# soc-conn.net
KiCad netlist of a schematic drawn in Altium Designer
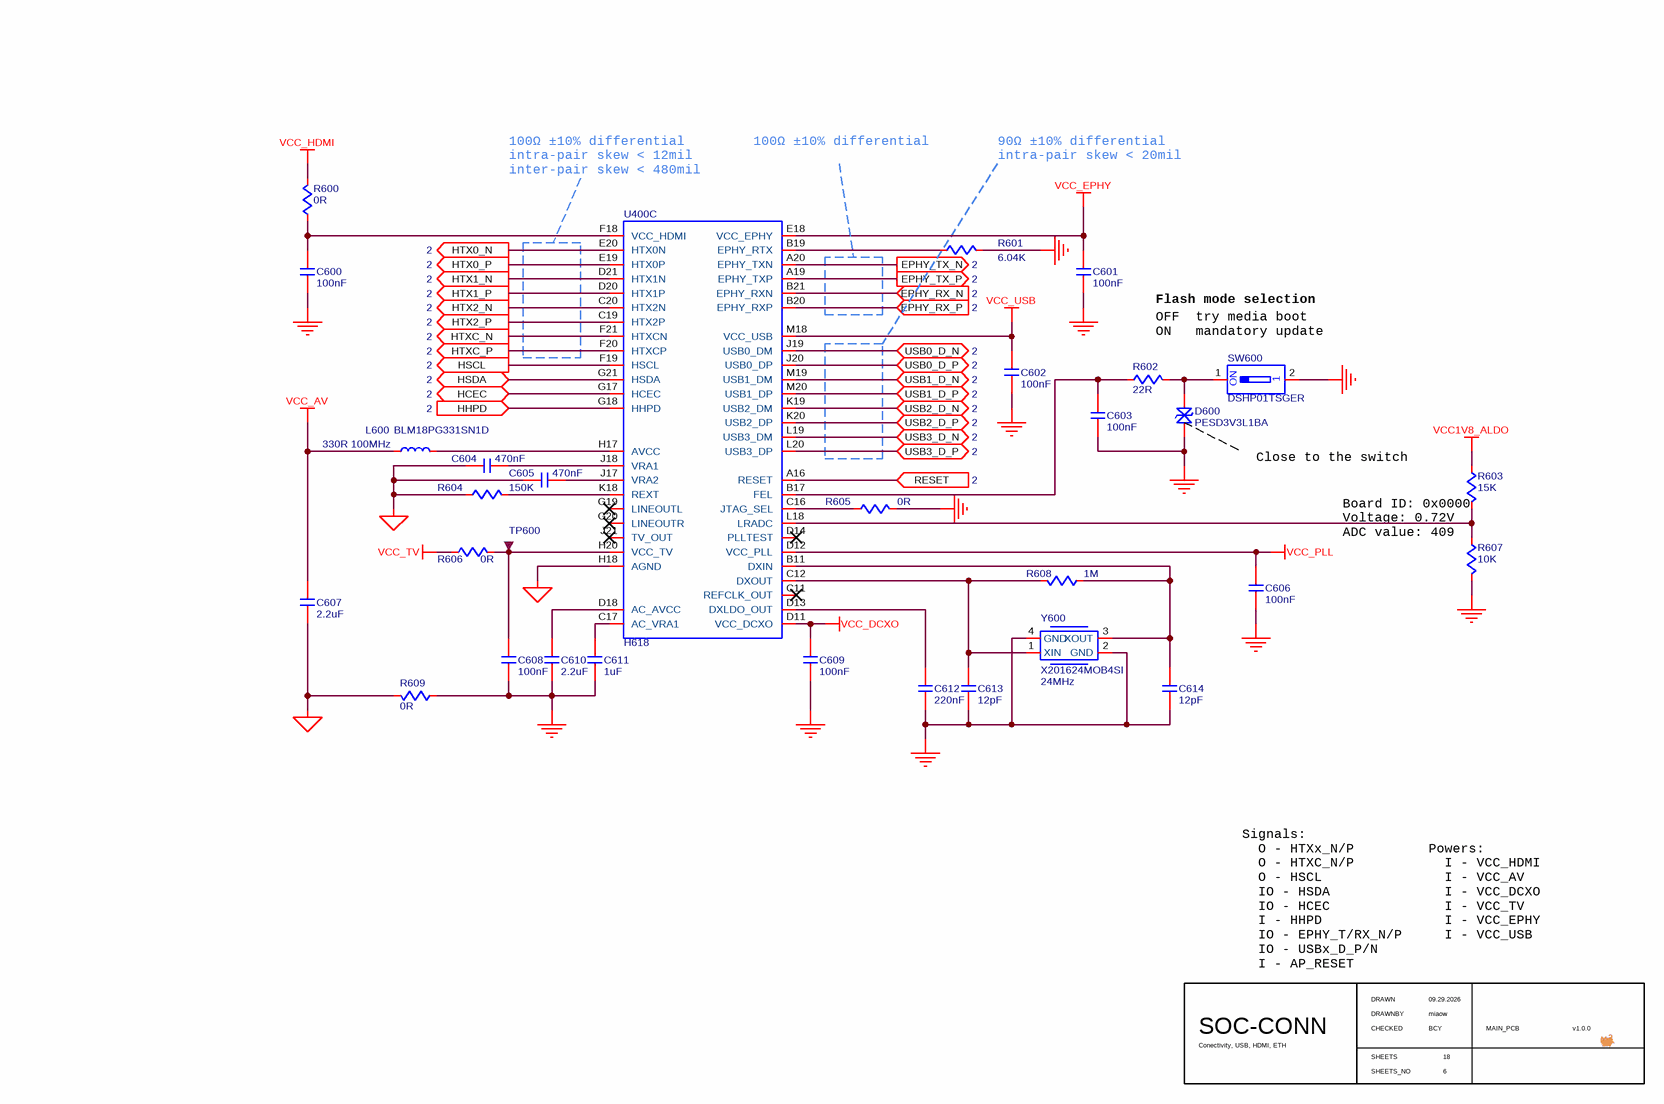
[diagram p0: soc-conn.schdoc]

(export (version "E")
  (design (tool "Eeschema 10.0.6"))
  (components
    (comp (ref "C600")
      (value "100nF")
      (footprint "mw:C0201")
      (fields (field (name "VOLTAGE") "10V") (field (name "Comment") "C-NOMO"))
      (libsource (lib "mw") (part "C-NOMO"))
    )
    (comp (ref "C601")
      (value "100nF")
      (footprint "mw:C0201")
      (fields (field (name "VOLTAGE") "10V") (field (name "Comment") "C-NOMO"))
      (libsource (lib "mw") (part "C-NOMO"))
    )
    (comp (ref "C602")
      (value "100nF")
      (footprint "mw:C0201")
      (fields (field (name "VOLTAGE") "10V") (field (name "Comment") "C-NOMO"))
      (libsource (lib "mw") (part "C-NOMO"))
    )
    (comp (ref "C603")
      (value "100nF")
      (footprint "mw:C0402")
      (fields (field (name "VOLTAGE") "50V") (field (name "Comment") "C-NOMO"))
      (libsource (lib "mw") (part "C-NOMO"))
    )
    (comp (ref "C604")
      (value "470nF")
      (footprint "mw:C0201")
      (fields (field (name "VOLTAGE") "6.3V") (field (name "Comment") "C-NOMO"))
      (libsource (lib "mw") (part "C-NOMO"))
    )
    (comp (ref "C605")
      (value "470nF")
      (footprint "mw:C0201")
      (fields (field (name "VOLTAGE") "6.3V") (field (name "Comment") "C-NOMO"))
      (libsource (lib "mw") (part "C-NOMO"))
    )
    (comp (ref "C606")
      (value "100nF")
      (footprint "mw:C0201")
      (fields (field (name "VOLTAGE") "10V") (field (name "Comment") "C-NOMO"))
      (libsource (lib "mw") (part "C-NOMO"))
    )
    (comp (ref "C607")
      (value "2.2uF")
      (footprint "mw:C0402")
      (fields (field (name "VOLTAGE") "6.3V") (field (name "Comment") "C-NOMO"))
      (libsource (lib "mw") (part "C-NOMO"))
    )
    (comp (ref "C608")
      (value "100nF")
      (footprint "mw:C0201")
      (fields (field (name "VOLTAGE") "10V") (field (name "Comment") "C-NOMO"))
      (libsource (lib "mw") (part "C-NOMO"))
    )
    (comp (ref "C609")
      (value "100nF")
      (footprint "mw:C0201")
      (fields (field (name "VOLTAGE") "10V") (field (name "Comment") "C-NOMO"))
      (libsource (lib "mw") (part "C-NOMO"))
    )
    (comp (ref "C610")
      (value "2.2uF")
      (footprint "mw:C0402")
      (fields (field (name "VOLTAGE") "6.3V") (field (name "Comment") "C-NOMO"))
      (libsource (lib "mw") (part "C-NOMO"))
    )
    (comp (ref "C611")
      (value "1uF")
      (footprint "mw:C0201")
      (fields (field (name "VOLTAGE") "6.3V") (field (name "Comment") "C-NOMO"))
      (libsource (lib "mw") (part "C-NOMO"))
    )
    (comp (ref "C612")
      (value "220nF")
      (footprint "mw:C0201")
      (fields (field (name "VOLTAGE") "6.3V") (field (name "Comment") "C-NOMO"))
      (libsource (lib "mw") (part "C-NOMO"))
    )
    (comp (ref "C613")
      (value "12pF")
      (footprint "mw:C0402")
      (fields (field (name "VOLTAGE") "50V") (field (name "Comment") "C-NOMO"))
      (libsource (lib "mw") (part "C-NOMO"))
    )
    (comp (ref "C614")
      (value "12pF")
      (footprint "mw:C0402")
      (fields (field (name "VOLTAGE") "50V") (field (name "Comment") "C-NOMO"))
      (libsource (lib "mw") (part "C-NOMO"))
    )
    (comp (ref "D600")
      (value "PESD3V3L1BA")
      (footprint "mw:PESD3V3L1BA")
      (description "TVS/ESD - 1 ch, 3.3V, 4V, 100pF@1MHz, 30KV")
      (libsource (lib "mw") (part "PESD3V3L1BA"))
    )
    (comp (ref "L600")
      (value "BLM18PG331SN1D")
      (footprint "mw:L0603")
      (fields (field (name "ALTIUM_VALUE") "330R 100MHz") (field (name "PUBLISHER") "Altium Limited"))
      (libsource (lib "mw") (part "L"))
    )
    (comp (ref "R600")
      (value "0R")
      (footprint "mw:R0402")
      (fields (field (name "Comment") "R"))
      (libsource (lib "mw") (part "R"))
    )
    (comp (ref "R601")
      (value "6.04K")
      (footprint "mw:R0402")
      (fields (field (name "Comment") "R"))
      (libsource (lib "mw") (part "R"))
    )
    (comp (ref "R602")
      (value "22R")
      (footprint "mw:R0402")
      (fields (field (name "Comment") "R"))
      (libsource (lib "mw") (part "R"))
    )
    (comp (ref "R603")
      (value "15K")
      (footprint "mw:R0402")
      (fields (field (name "Comment") "R"))
      (libsource (lib "mw") (part "R"))
    )
    (comp (ref "R604")
      (value "150K")
      (footprint "mw:R0402")
      (fields (field (name "Comment") "R"))
      (libsource (lib "mw") (part "R"))
    )
    (comp (ref "R605")
      (value "0R")
      (footprint "mw:R0402")
      (fields (field (name "Comment") "R"))
      (libsource (lib "mw") (part "R"))
    )
    (comp (ref "R606")
      (value "0R")
      (footprint "mw:R0402")
      (fields (field (name "Comment") "R"))
      (libsource (lib "mw") (part "R"))
    )
    (comp (ref "R607")
      (value "10K")
      (footprint "mw:R0402")
      (fields (field (name "Comment") "R"))
      (libsource (lib "mw") (part "R"))
    )
    (comp (ref "R608")
      (value "1M")
      (footprint "mw:R0402")
      (fields (field (name "Comment") "R"))
      (libsource (lib "mw") (part "R"))
    )
    (comp (ref "R609")
      (value "0R")
      (footprint "mw:R0402")
      (fields (field (name "Comment") "R"))
      (libsource (lib "mw") (part "R"))
    )
    (comp (ref "SW600")
      (value "DSHP01TSGER")
      (footprint "mw:DSHP01TSGER")
      (description "SWITCH - SPST, 1ch")
      (libsource (lib "mw") (part "DSHP01TSGER"))
    )
    (comp (ref "TP600") (value "TP") (footprint "mw:TP") (libsource (lib "mw") (part "TP")))
    (comp (ref "U400")
      (value "H618")
      (footprint "mw:H618")
      (description "SOC")
      (libsource (lib "mw") (part "H618"))
    )
    (comp (ref "Y600")
      (value "X201624MOB4SI")
      (footprint "mw:X201624MOB4SI")
      (description "XTAL - passive, 24MHz, ±10ppm, 12pF")
      (fields (field (name "ALTIUM_VALUE") "24MHz"))
      (libsource (lib "mw") (part "X201624MOB4SI"))
    )
  )
  (nets
    (net (code "1") (name "/EPHY_RX_N") (class "Default")
      (node (ref "U400") (pin "B21") (pinfunction "EPHY_RXN_B21") (pintype "passive"))
    )
    (net (code "2") (name "/EPHY_RX_P") (class "Default")
      (node (ref "U400") (pin "B20") (pinfunction "EPHY_RXP_B20") (pintype "passive"))
    )
    (net (code "3") (name "/EPHY_TX_N") (class "Default")
      (node (ref "U400") (pin "A20") (pinfunction "EPHY_TXN_A20") (pintype "passive"))
    )
    (net (code "4") (name "/EPHY_TX_P") (class "Default")
      (node (ref "U400") (pin "A19") (pinfunction "EPHY_TXP_A19") (pintype "passive"))
    )
    (net (code "5") (name "/HCEC") (class "Default")
      (node (ref "U400") (pin "G17") (pinfunction "HCEC_G17") (pintype "passive"))
    )
    (net (code "6") (name "/HHPD") (class "Default")
      (node (ref "U400") (pin "G18") (pinfunction "HHPD_G18") (pintype "passive"))
    )
    (net (code "7") (name "/HSCL") (class "Default")
      (node (ref "U400") (pin "F19") (pinfunction "HSCL_F19") (pintype "passive"))
    )
    (net (code "8") (name "/HSDA") (class "Default")
      (node (ref "U400") (pin "G21") (pinfunction "HSDA_G21") (pintype "passive"))
    )
    (net (code "9") (name "/HTX0_N") (class "Default")
      (node (ref "U400") (pin "E20") (pinfunction "HTX0N_E20") (pintype "passive"))
    )
    (net (code "10") (name "/HTX0_P") (class "Default")
      (node (ref "U400") (pin "E19") (pinfunction "HTX0P_E19") (pintype "passive"))
    )
    (net (code "11") (name "/HTX1_N") (class "Default")
      (node (ref "U400") (pin "D21") (pinfunction "HTX1N_D21") (pintype "passive"))
    )
    (net (code "12") (name "/HTX1_P") (class "Default")
      (node (ref "U400") (pin "D20") (pinfunction "HTX1P_D20") (pintype "passive"))
    )
    (net (code "13") (name "/HTX2_N") (class "Default")
      (node (ref "U400") (pin "C20") (pinfunction "HTX2N_C20") (pintype "passive"))
    )
    (net (code "14") (name "/HTX2_P") (class "Default")
      (node (ref "U400") (pin "C19") (pinfunction "HTX2P_C19") (pintype "passive"))
    )
    (net (code "15") (name "/HTXC_N") (class "Default")
      (node (ref "U400") (pin "F21") (pinfunction "HTXCN_F21") (pintype "passive"))
    )
    (net (code "16") (name "/HTXC_P") (class "Default")
      (node (ref "U400") (pin "F20") (pinfunction "HTXCP_F20") (pintype "passive"))
    )
    (net (code "17") (name "/RESET") (class "Default")
      (node (ref "U400") (pin "A16") (pinfunction "RESET_A16") (pintype "passive"))
    )
    (net (code "18") (name "/USB0_D_N") (class "Default")
      (node (ref "U400") (pin "J19") (pinfunction "USB0_DM_J19") (pintype "passive"))
    )
    (net (code "19") (name "/USB0_D_P") (class "Default")
      (node (ref "U400") (pin "J20") (pinfunction "USB0_DP_J20") (pintype "passive"))
    )
    (net (code "20") (name "/USB1_D_N") (class "Default")
      (node (ref "U400") (pin "M19") (pinfunction "USB1_DM_M19") (pintype "passive"))
    )
    (net (code "21") (name "/USB1_D_P") (class "Default")
      (node (ref "U400") (pin "M20") (pinfunction "USB1_DP_M20") (pintype "passive"))
    )
    (net (code "22") (name "/USB2_D_N") (class "Default")
      (node (ref "U400") (pin "K19") (pinfunction "USB2_DM_K19") (pintype "passive"))
    )
    (net (code "23") (name "/USB2_D_P") (class "Default")
      (node (ref "U400") (pin "K20") (pinfunction "USB2_DP_K20") (pintype "passive"))
    )
    (net (code "24") (name "/USB3_D_N") (class "Default")
      (node (ref "U400") (pin "L19") (pinfunction "USB3_DM_L19") (pintype "passive"))
    )
    (net (code "25") (name "/USB3_D_P") (class "Default")
      (node (ref "U400") (pin "L20") (pinfunction "USB3_DP_L20") (pintype "passive"))
    )
    (net (code "26") (name "AGND") (class "Default")
      (node (ref "C604") (pin "2") (pinfunction "2_2") (pintype "passive"))
      (node (ref "C605") (pin "2") (pinfunction "2_2") (pintype "passive"))
      (node (ref "C607") (pin "1") (pinfunction "1_1") (pintype "passive"))
      (node (ref "R604") (pin "2") (pinfunction "2_2") (pintype "passive"))
      (node (ref "R609") (pin "1") (pinfunction "1_1") (pintype "passive"))
      (node (ref "U400") (pin "H18") (pinfunction "AGND_H18") (pintype "passive"))
    )
    (net (code "27") (name "GND") (class "Default")
      (node (ref "C600") (pin "2") (pinfunction "2_2") (pintype "passive"))
      (node (ref "C601") (pin "2") (pinfunction "2_2") (pintype "passive"))
      (node (ref "C602") (pin "2") (pinfunction "2_2") (pintype "passive"))
      (node (ref "C603") (pin "2") (pinfunction "2_2") (pintype "passive"))
      (node (ref "C606") (pin "2") (pinfunction "2_2") (pintype "passive"))
      (node (ref "C608") (pin "2") (pinfunction "2_2") (pintype "passive"))
      (node (ref "C609") (pin "2") (pinfunction "2_2") (pintype "passive"))
      (node (ref "C610") (pin "1") (pinfunction "1_1") (pintype "passive"))
      (node (ref "C611") (pin "1") (pinfunction "1_1") (pintype "passive"))
      (node (ref "C612") (pin "2") (pinfunction "2_2") (pintype "passive"))
      (node (ref "C613") (pin "2") (pinfunction "2_2") (pintype "passive"))
      (node (ref "C614") (pin "2") (pinfunction "2_2") (pintype "passive"))
      (node (ref "D600") (pin "1") (pinfunction "1_1") (pintype "passive"))
      (node (ref "R601") (pin "1") (pinfunction "1_1") (pintype "passive"))
      (node (ref "R605") (pin "1") (pinfunction "1_1") (pintype "passive"))
      (node (ref "R607") (pin "1") (pinfunction "1_1") (pintype "passive"))
      (node (ref "R609") (pin "2") (pinfunction "2_2") (pintype "passive"))
      (node (ref "SW600") (pin "2") (pinfunction "2_2") (pintype "passive"))
      (node (ref "Y600") (pin "2") (pinfunction "GND_2") (pintype "passive"))
      (node (ref "Y600") (pin "4") (pinfunction "GND_4") (pintype "passive"))
    )
    (net (code "28") (name "Net-(D600-Pad2)") (class "Default")
      (node (ref "D600") (pin "2") (pinfunction "2_2") (pintype "passive"))
      (node (ref "R602") (pin "1") (pinfunction "1_1") (pintype "passive"))
      (node (ref "SW600") (pin "1") (pinfunction "1_1") (pintype "passive"))
    )
    (net (code "29") (name "Net-(U400C-AC_AVCC)") (class "Default")
      (node (ref "C610") (pin "2") (pinfunction "2_2") (pintype "passive"))
      (node (ref "U400") (pin "D18") (pinfunction "AC_AVCC_D18") (pintype "passive"))
    )
    (net (code "30") (name "Net-(U400C-AC_VRA1)") (class "Default")
      (node (ref "C611") (pin "2") (pinfunction "2_2") (pintype "passive"))
      (node (ref "U400") (pin "C17") (pinfunction "AC_VRA1_C17") (pintype "passive"))
    )
    (net (code "31") (name "Net-(U400C-AVCC)") (class "Default")
      (node (ref "L600") (pin "2") (pinfunction "2_2") (pintype "passive"))
      (node (ref "U400") (pin "H17") (pinfunction "AVCC_H17") (pintype "passive"))
    )
    (net (code "32") (name "Net-(U400C-DXIN)") (class "Default")
      (node (ref "C614") (pin "1") (pinfunction "1_1") (pintype "passive"))
      (node (ref "R608") (pin "2") (pinfunction "2_2") (pintype "passive"))
      (node (ref "U400") (pin "B11") (pinfunction "DXIN_B11") (pintype "passive"))
      (node (ref "Y600") (pin "3") (pinfunction "XOUT_3") (pintype "passive"))
    )
    (net (code "33") (name "Net-(U400C-DXLDO_OUT)") (class "Default")
      (node (ref "C612") (pin "1") (pinfunction "1_1") (pintype "passive"))
      (node (ref "U400") (pin "D13") (pinfunction "DXLDO_OUT_D13") (pintype "passive"))
    )
    (net (code "34") (name "Net-(U400C-DXOUT)") (class "Default")
      (node (ref "C613") (pin "1") (pinfunction "1_1") (pintype "passive"))
      (node (ref "R608") (pin "1") (pinfunction "1_1") (pintype "passive"))
      (node (ref "U400") (pin "C12") (pinfunction "DXOUT_C12") (pintype "passive"))
      (node (ref "Y600") (pin "1") (pinfunction "XIN_1") (pintype "passive"))
    )
    (net (code "35") (name "Net-(U400C-EPHY_RTX)") (class "Default")
      (node (ref "R601") (pin "2") (pinfunction "2_2") (pintype "passive"))
      (node (ref "U400") (pin "B19") (pinfunction "EPHY_RTX_B19") (pintype "passive"))
    )
    (net (code "36") (name "Net-(U400C-FEL)") (class "Default")
      (node (ref "C603") (pin "1") (pinfunction "1_1") (pintype "passive"))
      (node (ref "R602") (pin "2") (pinfunction "2_2") (pintype "passive"))
      (node (ref "U400") (pin "B17") (pinfunction "FEL_B17") (pintype "passive"))
    )
    (net (code "37") (name "Net-(U400C-JTAG_SEL)") (class "Default")
      (node (ref "R605") (pin "2") (pinfunction "2_2") (pintype "passive"))
      (node (ref "U400") (pin "C16") (pinfunction "JTAG_SEL_C16") (pintype "passive"))
    )
    (net (code "38") (name "Net-(U400C-LRADC)") (class "Default")
      (node (ref "R603") (pin "1") (pinfunction "1_1") (pintype "passive"))
      (node (ref "R607") (pin "2") (pinfunction "2_2") (pintype "passive"))
      (node (ref "U400") (pin "L18") (pinfunction "LRADC_L18") (pintype "passive"))
    )
    (net (code "39") (name "Net-(U400C-REXT)") (class "Default")
      (node (ref "R604") (pin "1") (pinfunction "1_1") (pintype "passive"))
      (node (ref "U400") (pin "K18") (pinfunction "REXT_K18") (pintype "passive"))
    )
    (net (code "40") (name "Net-(U400C-VCC_HDMI)") (class "Default")
      (node (ref "C600") (pin "1") (pinfunction "1_1") (pintype "passive"))
      (node (ref "R600") (pin "2") (pinfunction "2_2") (pintype "passive"))
      (node (ref "U400") (pin "F18") (pinfunction "VCC_HDMI_F18") (pintype "passive"))
    )
    (net (code "41") (name "Net-(U400C-VCC_TV)") (class "Default")
      (node (ref "C608") (pin "1") (pinfunction "1_1") (pintype "passive"))
      (node (ref "R606") (pin "1") (pinfunction "1_1") (pintype "passive"))
      (node (ref "TP600") (pin "0") (pintype "passive"))
      (node (ref "U400") (pin "H20") (pinfunction "VCC_TV_H20") (pintype "passive"))
    )
    (net (code "42") (name "Net-(U400C-VRA1)") (class "Default")
      (node (ref "C604") (pin "1") (pinfunction "1_1") (pintype "passive"))
      (node (ref "U400") (pin "J18") (pinfunction "VRA1_J18") (pintype "passive"))
    )
    (net (code "43") (name "Net-(U400C-VRA2)") (class "Default")
      (node (ref "C605") (pin "1") (pinfunction "1_1") (pintype "passive"))
      (node (ref "U400") (pin "J17") (pinfunction "VRA2_J17") (pintype "passive"))
    )
    (net (code "44") (name "VCC1V8_ALDO") (class "Default")
      (node (ref "R603") (pin "2") (pinfunction "2_2") (pintype "passive"))
    )
    (net (code "45") (name "VCC_AV") (class "Default")
      (node (ref "C607") (pin "2") (pinfunction "2_2") (pintype "passive"))
      (node (ref "L600") (pin "1") (pinfunction "1_1") (pintype "passive"))
    )
    (net (code "46") (name "VCC_DCXO") (class "Default")
      (node (ref "C609") (pin "1") (pinfunction "1_1") (pintype "passive"))
      (node (ref "U400") (pin "D11") (pinfunction "VCC_DCXO_D11") (pintype "passive"))
    )
    (net (code "47") (name "VCC_EPHY") (class "Default")
      (node (ref "C601") (pin "1") (pinfunction "1_1") (pintype "passive"))
      (node (ref "U400") (pin "E18") (pinfunction "VCC_EPHY_E18") (pintype "passive"))
    )
    (net (code "48") (name "VCC_HDMI") (class "Default")
      (node (ref "R600") (pin "1") (pinfunction "1_1") (pintype "passive"))
    )
    (net (code "49") (name "VCC_PLL") (class "Default")
      (node (ref "C606") (pin "1") (pinfunction "1_1") (pintype "passive"))
      (node (ref "U400") (pin "D12") (pinfunction "VCC_PLL_D12") (pintype "passive"))
    )
    (net (code "50") (name "VCC_TV") (class "Default")
      (node (ref "R606") (pin "2") (pinfunction "2_2") (pintype "passive"))
    )
    (net (code "51") (name "VCC_USB") (class "Default")
      (node (ref "C602") (pin "1") (pinfunction "1_1") (pintype "passive"))
      (node (ref "U400") (pin "M18") (pinfunction "VCC_USB_M18") (pintype "passive"))
    )
    (net (code "52") (name "unconnected-(U400C-LINEOUTL-PadG19)") (class "Default")
      (node (ref "U400") (pin "G19") (pinfunction "LINEOUTL_G19") (pintype "passive+no_connect"))
    )
    (net (code "53") (name "unconnected-(U400C-LINEOUTR-PadG20)") (class "Default")
      (node (ref "U400") (pin "G20") (pinfunction "LINEOUTR_G20") (pintype "passive+no_connect"))
    )
    (net (code "54") (name "unconnected-(U400C-PLLTEST-PadD14)") (class "Default")
      (node (ref "U400") (pin "D14") (pinfunction "PLLTEST_D14") (pintype "passive+no_connect"))
    )
    (net (code "55") (name "unconnected-(U400C-REFCLK_OUT-PadC11)") (class "Default")
      (node (ref "U400") (pin "C11") (pinfunction "REFCLK_OUT_C11") (pintype "passive+no_connect"))
    )
    (net (code "56") (name "unconnected-(U400C-TV_OUT-PadJ21)") (class "Default")
      (node (ref "U400") (pin "J21") (pinfunction "TV_OUT_J21") (pintype "passive+no_connect"))
    )
  )
)
